# STM32F103RCT6.net
KiCad netlist of a schematic drawn in Altium Designer
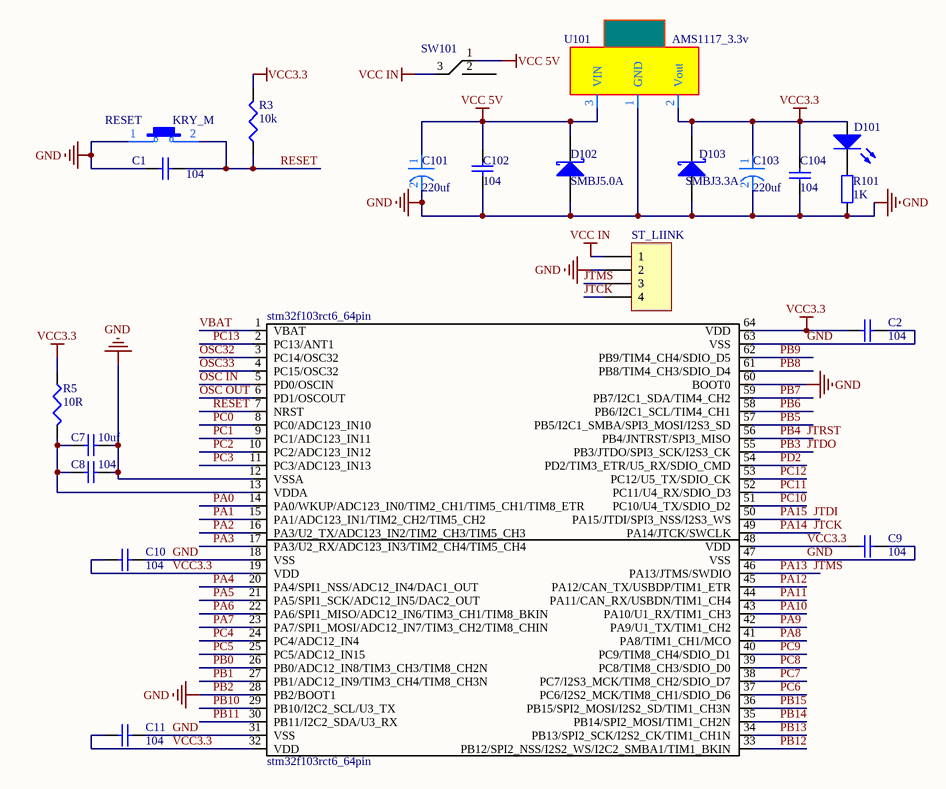
[diagram p0: STM32F103RCT6最小系统.SchDoc]

(export (version "E")
  (design (tool "Eeschema 10.0.6"))
  (components
    (comp (ref "C1")
      (value "104")
      (footprint "C1206")
      (description "Capacitor (Semiconductor SIM Model)")
      (fields (field (name "Comment") "Cap Semi") (field (name "PUBLISHER") "Altium Limited"))
      (libsource (lib "Miscellaneous Devices") (part "Cap Semi"))
    )
    (comp (ref "C2")
      (value "104")
      (footprint "C1206")
      (description "Capacitor (Semiconductor SIM Model)")
      (fields (field (name "Comment") "Cap Semi") (field (name "PUBLISHER") "Altium Limited"))
      (libsource (lib "Miscellaneous Devices") (part "Cap Semi"))
    )
    (comp (ref "C7")
      (value "10uf")
      (footprint "C1206")
      (description "Capacitor (Semiconductor SIM Model)")
      (fields (field (name "Comment") "Cap Semi") (field (name "PUBLISHER") "Altium Limited"))
      (libsource (lib "Miscellaneous Devices") (part "Cap Semi"))
    )
    (comp (ref "C8")
      (value "104")
      (footprint "C1206")
      (description "Capacitor (Semiconductor SIM Model)")
      (fields (field (name "Comment") "Cap Semi") (field (name "PUBLISHER") "Altium Limited"))
      (libsource (lib "Miscellaneous Devices") (part "Cap Semi"))
    )
    (comp (ref "C9")
      (value "104")
      (footprint "C1206")
      (description "Capacitor (Semiconductor SIM Model)")
      (fields (field (name "Comment") "Cap Semi") (field (name "PUBLISHER") "Altium Limited"))
      (libsource (lib "Miscellaneous Devices") (part "Cap Semi"))
    )
    (comp (ref "C10")
      (value "104")
      (footprint "C1206")
      (description "Capacitor (Semiconductor SIM Model)")
      (fields (field (name "Comment") "Cap Semi") (field (name "PUBLISHER") "Altium Limited"))
      (libsource (lib "Miscellaneous Devices") (part "Cap Semi"))
    )
    (comp (ref "C11")
      (value "104")
      (footprint "C1206")
      (description "Capacitor (Semiconductor SIM Model)")
      (fields (field (name "Comment") "Cap Semi") (field (name "PUBLISHER") "Altium Limited"))
      (libsource (lib "Miscellaneous Devices") (part "Cap Semi"))
    )
    (comp (ref "C101")
      (value "220uf")
      (footprint "电解电容")
      (fields (field (name "Comment") "电解电容"))
      (libsource (lib "stm8s105c6最小系统") (part "电解电容"))
    )
    (comp (ref "C102")
      (value "104")
      (footprint "C1206")
      (description "Capacitor (Semiconductor SIM Model)")
      (fields (field (name "Comment") "Cap Semi") (field (name "PUBLISHER") "Altium Limited"))
      (libsource (lib "Miscellaneous Devices") (part "Cap Semi"))
    )
    (comp (ref "C103")
      (value "220uf")
      (footprint "电解电容")
      (fields (field (name "Comment") "电解电容"))
      (libsource (lib "stm8s105c6最小系统") (part "电解电容"))
    )
    (comp (ref "C104")
      (value "104")
      (footprint "C1206")
      (description "Capacitor (Semiconductor SIM Model)")
      (fields (field (name "Comment") "Cap Semi") (field (name "PUBLISHER") "Altium Limited"))
      (libsource (lib "Miscellaneous Devices") (part "Cap Semi"))
    )
    (comp (ref "D101")
      (value "LED")
      (footprint "3.5X2.8X1.9")
      (description "发光二极管")
      (libsource (lib "常用器件") (part "LED_"))
    )
    (comp (ref "D102")
      (value "SMBJ5.0A")
      (footprint "SMB")
      (description "Schottky Diode")
      (fields (field (name "PUBLISHER") "Altium Limited"))
      (libsource (lib "Miscellaneous Devices") (part "D Schottky"))
    )
    (comp (ref "D103")
      (value "SMBJ3.3A")
      (footprint "SMB")
      (description "Schottky Diode")
      (fields (field (name "PUBLISHER") "Altium Limited"))
      (libsource (lib "Miscellaneous Devices") (part "D Schottky"))
    )
    (comp (ref "R3")
      (value "10k")
      (footprint "C1206")
      (description "Resistor")
      (fields (field (name "Comment") "Res3") (field (name "PUBLISHER") "Altium Limited"))
      (libsource (lib "Miscellaneous Devices") (part "Res3"))
    )
    (comp (ref "R5")
      (value "10R")
      (footprint "C1206")
      (description "Resistor")
      (fields (field (name "Comment") "Res3") (field (name "PUBLISHER") "Altium Limited"))
      (libsource (lib "Miscellaneous Devices") (part "Res3"))
    )
    (comp (ref "R101")
      (value "1K")
      (footprint "AXIAL-0.4")
      (description "Resistor")
      (fields (field (name "Comment") "Res2") (field (name "PUBLISHER") "Altium Limited"))
      (libsource (lib "Miscellaneous Devices") (part "Res2"))
    )
    (comp (ref "RESET") (value "KRY_M") (footprint "SW_4c") (libsource (lib "stm8s105c6最小系统") (part "SW_4t")))
    (comp (ref "stm32f103rct6_64pin")
      (value "stm32f103rct6_64pin")
      (footprint "stm32f103rct6_64pin")
      (libsource (lib "My Library(SOP)") (part "stm32f103rct6_64pin"))
    )
    (comp (ref "ST_LIINK")
      (value "Header 4")
      (footprint "HDR1X4")
      (description "Header, 4-Pin")
      (fields (field (name "PUBLISHER") "Altium Limited"))
      (libsource (lib "Miscellaneous Connectors") (part "Header 4"))
    )
    (comp (ref "SW101") (value "三脚开关") (footprint "三脚开关") (libsource (lib "正弦波发生器") (part "三脚开关")))
    (comp (ref "U101")
      (value "AMS1117_3.3v")
      (footprint "AMS1117_3.3V")
      (libsource (lib "stm8s105c6最小系统") (part "AMS1117_3.3v"))
    )
  )
  (nets
    (net (code "1") (name "/JTCK") (class "Default")
      (node (ref "ST_LIINK") (pin "4") (pinfunction "4_4") (pintype "passive"))
      (node (ref "stm32f103rct6_64pin") (pin "49") (pinfunction "PA14/JTCK/SWCLK_49") (pintype "passive"))
    )
    (net (code "2") (name "/JTDI") (class "Default")
      (node (ref "stm32f103rct6_64pin") (pin "50") (pinfunction "PA15/JTDI/SPI3_NSS/I2S3_WS_50") (pintype "passive"))
    )
    (net (code "3") (name "/JTDO") (class "Default")
      (node (ref "stm32f103rct6_64pin") (pin "55") (pinfunction "PB3/JTDO/SPI3_SCK/I2S3_CK_55") (pintype "passive"))
    )
    (net (code "4") (name "/JTMS") (class "Default")
      (node (ref "ST_LIINK") (pin "3") (pinfunction "3_3") (pintype "passive"))
      (node (ref "stm32f103rct6_64pin") (pin "46") (pinfunction "PA13/JTMS/SWDIO_46") (pintype "passive"))
    )
    (net (code "5") (name "/JTRST") (class "Default")
      (node (ref "stm32f103rct6_64pin") (pin "56") (pinfunction "PB4/JNTRST/SPI3_MISO_56") (pintype "passive"))
    )
    (net (code "6") (name "/OSC IN") (class "Default")
      (node (ref "stm32f103rct6_64pin") (pin "5") (pinfunction "PD0/OSCIN_5") (pintype "passive"))
    )
    (net (code "7") (name "/OSC OUT") (class "Default")
      (node (ref "stm32f103rct6_64pin") (pin "6") (pinfunction "PD1/OSCOUT_6") (pintype "passive"))
    )
    (net (code "8") (name "/OSC32") (class "Default")
      (node (ref "stm32f103rct6_64pin") (pin "3") (pinfunction "PC14/OSC32_3") (pintype "passive"))
    )
    (net (code "9") (name "/OSC33") (class "Default")
      (node (ref "stm32f103rct6_64pin") (pin "4") (pinfunction "PC15/OSC32_4") (pintype "passive"))
    )
    (net (code "10") (name "/PA0") (class "Default")
      (node (ref "stm32f103rct6_64pin") (pin "14") (pinfunction "PA0/WKUP/ADC123_IN0/TIM2_CH1/TIM5_CH1/TIM8_ETR_14") (pintype "passive"))
    )
    (net (code "11") (name "/PA1") (class "Default")
      (node (ref "stm32f103rct6_64pin") (pin "15") (pinfunction "PA1/ADC123_IN1/TIM2_CH2/TIM5_CH2_15") (pintype "passive"))
    )
    (net (code "12") (name "/PA2") (class "Default")
      (node (ref "stm32f103rct6_64pin") (pin "16") (pinfunction "PA3/U2_TX/ADC123_IN2/TIM2_CH3/TIM5_CH3_16") (pintype "passive"))
    )
    (net (code "13") (name "/PA3") (class "Default")
      (node (ref "stm32f103rct6_64pin") (pin "17") (pinfunction "PA3/U2_RX/ADC123_IN3/TIM2_CH4/TIM5_CH4_17") (pintype "passive"))
    )
    (net (code "14") (name "/PA4") (class "Default")
      (node (ref "stm32f103rct6_64pin") (pin "20") (pinfunction "PA4/SPI1_NSS/ADC12_IN4/DAC1_OUT_20") (pintype "passive"))
    )
    (net (code "15") (name "/PA5") (class "Default")
      (node (ref "stm32f103rct6_64pin") (pin "21") (pinfunction "PA5/SPI1_SCK/ADC12_IN5/DAC2_OUT_21") (pintype "passive"))
    )
    (net (code "16") (name "/PA6") (class "Default")
      (node (ref "stm32f103rct6_64pin") (pin "22") (pinfunction "PA6/SPI1_MISO/ADC12_IN6/TIM3_CH1/TIM8_BKIN_22") (pintype "passive"))
    )
    (net (code "17") (name "/PA7") (class "Default")
      (node (ref "stm32f103rct6_64pin") (pin "23") (pinfunction "PA7/SPI1_MOSI/ADC12_IN7/TIM3_CH2/TIM8_CHIN_23") (pintype "passive"))
    )
    (net (code "18") (name "/PA8") (class "Default")
      (node (ref "stm32f103rct6_64pin") (pin "41") (pinfunction "PA8/TIM1_CH1/MCO_41") (pintype "passive"))
    )
    (net (code "19") (name "/PA9") (class "Default")
      (node (ref "stm32f103rct6_64pin") (pin "42") (pinfunction "PA9/U1_TX/TIM1_CH2_42") (pintype "passive"))
    )
    (net (code "20") (name "/PA10") (class "Default")
      (node (ref "stm32f103rct6_64pin") (pin "43") (pinfunction "PA10/U1_RX/TIM1_CH3_43") (pintype "passive"))
    )
    (net (code "21") (name "/PA11") (class "Default")
      (node (ref "stm32f103rct6_64pin") (pin "44") (pinfunction "PA11/CAN_RX/USBDN/TIM1_CH4_44") (pintype "passive"))
    )
    (net (code "22") (name "/PA12") (class "Default")
      (node (ref "stm32f103rct6_64pin") (pin "45") (pinfunction "PA12/CAN_TX/USBDP/TIM1_ETR_45") (pintype "passive"))
    )
    (net (code "23") (name "/PB0") (class "Default")
      (node (ref "stm32f103rct6_64pin") (pin "26") (pinfunction "PB0/ADC12_IN8/TIM3_CH3/TIM8_CH2N_26") (pintype "passive"))
    )
    (net (code "24") (name "/PB1") (class "Default")
      (node (ref "stm32f103rct6_64pin") (pin "27") (pinfunction "PB1/ADC12_IN9/TIM3_CH4/TIM8_CH3N_27") (pintype "passive"))
    )
    (net (code "25") (name "/PB5") (class "Default")
      (node (ref "stm32f103rct6_64pin") (pin "57") (pinfunction "PB5/I2C1_SMBA/SPI3_MOSI/I2S3_SD_57") (pintype "passive"))
    )
    (net (code "26") (name "/PB6") (class "Default")
      (node (ref "stm32f103rct6_64pin") (pin "58") (pinfunction "PB6/I2C1_SCL/TIM4_CH1_58") (pintype "passive"))
    )
    (net (code "27") (name "/PB7") (class "Default")
      (node (ref "stm32f103rct6_64pin") (pin "59") (pinfunction "PB7/I2C1_SDA/TIM4_CH2_59") (pintype "passive"))
    )
    (net (code "28") (name "/PB8") (class "Default")
      (node (ref "stm32f103rct6_64pin") (pin "61") (pinfunction "PB8/TIM4_CH3/SDIO_D4_61") (pintype "passive"))
    )
    (net (code "29") (name "/PB9") (class "Default")
      (node (ref "stm32f103rct6_64pin") (pin "62") (pinfunction "PB9/TIM4_CH4/SDIO_D5_62") (pintype "passive"))
    )
    (net (code "30") (name "/PB10") (class "Default")
      (node (ref "stm32f103rct6_64pin") (pin "29") (pinfunction "PB10/I2C2_SCL/U3_TX_29") (pintype "passive"))
    )
    (net (code "31") (name "/PB11") (class "Default")
      (node (ref "stm32f103rct6_64pin") (pin "30") (pinfunction "PB11/I2C2_SDA/U3_RX_30") (pintype "passive"))
    )
    (net (code "32") (name "/PB12") (class "Default")
      (node (ref "stm32f103rct6_64pin") (pin "33") (pinfunction "PB12/SPI2_NSS/I2S2_WS/I2C2_SMBA1/TIM1_BKIN_33") (pintype "passive"))
    )
    (net (code "33") (name "/PB13") (class "Default")
      (node (ref "stm32f103rct6_64pin") (pin "34") (pinfunction "PB13/SPI2_SCK/I2S2_CK/TIM1_CH1N_34") (pintype "passive"))
    )
    (net (code "34") (name "/PB14") (class "Default")
      (node (ref "stm32f103rct6_64pin") (pin "35") (pinfunction "PB14/SPI2_MOSI/TIM1_CH2N_35") (pintype "passive"))
    )
    (net (code "35") (name "/PB15") (class "Default")
      (node (ref "stm32f103rct6_64pin") (pin "36") (pinfunction "PB15/SPI2_MOSI/I2S2_SD/TIM1_CH3N_36") (pintype "passive"))
    )
    (net (code "36") (name "/PC0") (class "Default")
      (node (ref "stm32f103rct6_64pin") (pin "8") (pinfunction "PC0/ADC123_IN10_8") (pintype "passive"))
    )
    (net (code "37") (name "/PC1") (class "Default")
      (node (ref "stm32f103rct6_64pin") (pin "9") (pinfunction "PC1/ADC123_IN11_9") (pintype "passive"))
    )
    (net (code "38") (name "/PC2") (class "Default")
      (node (ref "stm32f103rct6_64pin") (pin "10") (pinfunction "PC2/ADC123_IN12_10") (pintype "passive"))
    )
    (net (code "39") (name "/PC3") (class "Default")
      (node (ref "stm32f103rct6_64pin") (pin "11") (pinfunction "PC3/ADC123_IN13_11") (pintype "passive"))
    )
    (net (code "40") (name "/PC4") (class "Default")
      (node (ref "stm32f103rct6_64pin") (pin "24") (pinfunction "PC4/ADC12_IN4_24") (pintype "passive"))
    )
    (net (code "41") (name "/PC5") (class "Default")
      (node (ref "stm32f103rct6_64pin") (pin "25") (pinfunction "PC5/ADC12_IN15_25") (pintype "passive"))
    )
    (net (code "42") (name "/PC6") (class "Default")
      (node (ref "stm32f103rct6_64pin") (pin "37") (pinfunction "PC6/I2S2_MCK/TIM8_CH1/SDIO_D6_37") (pintype "passive"))
    )
    (net (code "43") (name "/PC7") (class "Default")
      (node (ref "stm32f103rct6_64pin") (pin "38") (pinfunction "PC7/I2S3_MCK/TIM8_CH2/SDIO_D7_38") (pintype "passive"))
    )
    (net (code "44") (name "/PC8") (class "Default")
      (node (ref "stm32f103rct6_64pin") (pin "39") (pinfunction "PC8/TIM8_CH3/SDIO_D0_39") (pintype "passive"))
    )
    (net (code "45") (name "/PC9") (class "Default")
      (node (ref "stm32f103rct6_64pin") (pin "40") (pinfunction "PC9/TIM8_CH4/SDIO_D1_40") (pintype "passive"))
    )
    (net (code "46") (name "/PC10") (class "Default")
      (node (ref "stm32f103rct6_64pin") (pin "51") (pinfunction "PC10/U4_TX/SDIO_D2_51") (pintype "passive"))
    )
    (net (code "47") (name "/PC11") (class "Default")
      (node (ref "stm32f103rct6_64pin") (pin "52") (pinfunction "PC11/U4_RX/SDIO_D3_52") (pintype "passive"))
    )
    (net (code "48") (name "/PC12") (class "Default")
      (node (ref "stm32f103rct6_64pin") (pin "53") (pinfunction "PC12/U5_TX/SDIO_CK_53") (pintype "passive"))
    )
    (net (code "49") (name "/PC13") (class "Default")
      (node (ref "stm32f103rct6_64pin") (pin "2") (pinfunction "PC13/ANT1_2") (pintype "passive"))
    )
    (net (code "50") (name "/PD2") (class "Default")
      (node (ref "stm32f103rct6_64pin") (pin "54") (pinfunction "PD2/TIM3_ETR/U5_RX/SDIO_CMD_54") (pintype "passive"))
    )
    (net (code "51") (name "/RESET") (class "Default")
      (node (ref "C1") (pin "2") (pinfunction "2_2") (pintype "passive"))
      (node (ref "R3") (pin "1") (pinfunction "1_1") (pintype "passive"))
      (node (ref "RESET") (pin "2") (pinfunction "2_2") (pintype "passive"))
      (node (ref "stm32f103rct6_64pin") (pin "7") (pinfunction "NRST_7") (pintype "passive"))
    )
    (net (code "52") (name "/VBAT") (class "Default")
      (node (ref "stm32f103rct6_64pin") (pin "1") (pinfunction "VBAT_1") (pintype "passive"))
    )
    (net (code "53") (name "GND") (class "Default")
      (node (ref "C1") (pin "1") (pinfunction "1_1") (pintype "passive"))
      (node (ref "C10") (pin "1") (pinfunction "1_1") (pintype "passive"))
      (node (ref "C101") (pin "2") (pinfunction "2_2") (pintype "passive"))
      (node (ref "C102") (pin "1") (pinfunction "1_1") (pintype "passive"))
      (node (ref "C103") (pin "2") (pinfunction "2_2") (pintype "passive"))
      (node (ref "C104") (pin "1") (pinfunction "1_1") (pintype "passive"))
      (node (ref "C11") (pin "1") (pinfunction "1_1") (pintype "passive"))
      (node (ref "C2") (pin "1") (pinfunction "1_1") (pintype "passive"))
      (node (ref "C7") (pin "2") (pinfunction "2_2") (pintype "passive"))
      (node (ref "C8") (pin "1") (pinfunction "1_1") (pintype "passive"))
      (node (ref "C9") (pin "1") (pinfunction "1_1") (pintype "passive"))
      (node (ref "D102") (pin "1") (pinfunction "A_1") (pintype "passive"))
      (node (ref "D103") (pin "1") (pinfunction "A_1") (pintype "passive"))
      (node (ref "R101") (pin "1") (pinfunction "1_1") (pintype "passive"))
      (node (ref "RESET") (pin "1") (pinfunction "1_1") (pintype "passive"))
      (node (ref "ST_LIINK") (pin "2") (pinfunction "2_2") (pintype "passive"))
      (node (ref "U101") (pin "1") (pinfunction "GND_1") (pintype "passive"))
      (node (ref "stm32f103rct6_64pin") (pin "12") (pinfunction "VSSA_12") (pintype "passive"))
      (node (ref "stm32f103rct6_64pin") (pin "18") (pinfunction "VSS_18") (pintype "passive"))
      (node (ref "stm32f103rct6_64pin") (pin "28") (pinfunction "PB2/BOOT1_28") (pintype "passive"))
      (node (ref "stm32f103rct6_64pin") (pin "31") (pinfunction "VSS_31") (pintype "passive"))
      (node (ref "stm32f103rct6_64pin") (pin "47") (pinfunction "VSS_47") (pintype "passive"))
      (node (ref "stm32f103rct6_64pin") (pin "60") (pinfunction "BOOT0_60") (pintype "passive"))
      (node (ref "stm32f103rct6_64pin") (pin "63") (pinfunction "VSS_63") (pintype "passive"))
    )
    (net (code "54") (name "Net-(D101-K)") (class "Default")
      (node (ref "D101") (pin "2") (pinfunction "K_2") (pintype "passive"))
      (node (ref "R101") (pin "2") (pinfunction "2_2") (pintype "passive"))
    )
    (net (code "55") (name "Net-(stm32f103rct6_64pin-VDDA)") (class "Default")
      (node (ref "C7") (pin "1") (pinfunction "1_1") (pintype "passive"))
      (node (ref "C8") (pin "2") (pinfunction "2_2") (pintype "passive"))
      (node (ref "R5") (pin "2") (pinfunction "2_2") (pintype "passive"))
      (node (ref "stm32f103rct6_64pin") (pin "13") (pinfunction "VDDA_13") (pintype "passive"))
    )
    (net (code "56") (name "VCC 5V") (class "Default")
      (node (ref "C101") (pin "1") (pinfunction "1_1") (pintype "passive"))
      (node (ref "C102") (pin "2") (pinfunction "2_2") (pintype "passive"))
      (node (ref "D102") (pin "2") (pinfunction "K_2") (pintype "passive"))
      (node (ref "SW101") (pin "1") (pinfunction "1_1") (pintype "passive"))
      (node (ref "U101") (pin "3") (pinfunction "VIN_3") (pintype "passive"))
    )
    (net (code "57") (name "VCC IN") (class "Default")
      (node (ref "ST_LIINK") (pin "1") (pinfunction "1_1") (pintype "passive"))
      (node (ref "SW101") (pin "3") (pinfunction "3_3") (pintype "passive"))
    )
    (net (code "58") (name "VCC3.3") (class "Default")
      (node (ref "C10") (pin "2") (pinfunction "2_2") (pintype "passive"))
      (node (ref "C103") (pin "1") (pinfunction "1_1") (pintype "passive"))
      (node (ref "C104") (pin "2") (pinfunction "2_2") (pintype "passive"))
      (node (ref "C11") (pin "2") (pinfunction "2_2") (pintype "passive"))
      (node (ref "C2") (pin "2") (pinfunction "2_2") (pintype "passive"))
      (node (ref "C9") (pin "2") (pinfunction "2_2") (pintype "passive"))
      (node (ref "D101") (pin "1") (pinfunction "A_1") (pintype "passive"))
      (node (ref "D103") (pin "2") (pinfunction "K_2") (pintype "passive"))
      (node (ref "R3") (pin "2") (pinfunction "2_2") (pintype "passive"))
      (node (ref "R5") (pin "1") (pinfunction "1_1") (pintype "passive"))
      (node (ref "U101") (pin "2") (pinfunction "Vout_2") (pintype "passive"))
      (node (ref "stm32f103rct6_64pin") (pin "19") (pinfunction "VDD_19") (pintype "passive"))
      (node (ref "stm32f103rct6_64pin") (pin "32") (pinfunction "VDD_32") (pintype "passive"))
      (node (ref "stm32f103rct6_64pin") (pin "48") (pinfunction "VDD_48") (pintype "passive"))
      (node (ref "stm32f103rct6_64pin") (pin "64") (pinfunction "VDD_64") (pintype "passive"))
    )
    (net (code "59") (name "unconnected-(SW101-Pad2)") (class "Default")
      (node (ref "SW101") (pin "2") (pinfunction "2_2") (pintype "passive"))
    )
  )
)
